# BaoFengTRRSAdapter-Example.net
KiCad netlist of a schematic drawn in EAGLE
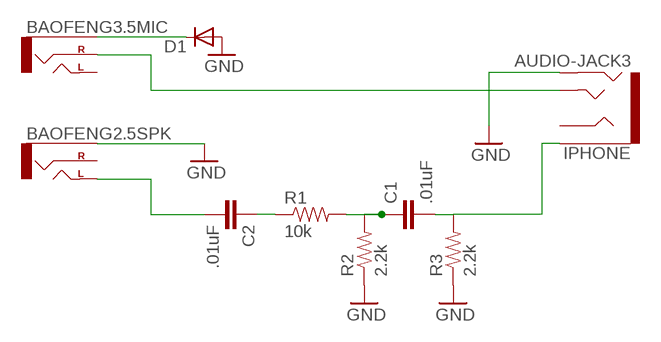
[diagram p0: schematic, sheet 1]

(export (version "E")
  (design (tool "Eeschema 10.0.6"))
  (components
    (comp (ref "BAOFENG2.5SPK")
      (value "AUDIO-JACK2.5MM")
      (footprint "eagle-import:STEREOJACK2.5MM_STEREOJACK2.5MM")
      (libsource (lib "eagle-import") (part "AUDIO-JACK2.5MM"))
    )
    (comp (ref "BAOFENG3.5MIC")
      (value "AUDIO-JACKHOLESONLY")
      (footprint "eagle-import:STEREOJACK2.5MM_SPECIAL_HOLES-ONLY")
      (libsource (lib "eagle-import") (part "AUDIO-JACKHOLESONLY"))
    )
    (comp (ref "C1")
      (value ".01uF")
      (footprint "eagle-import:0603-CAP")
      (libsource (lib "eagle-import") (part "CAP0603-CAP"))
    )
    (comp (ref "C2")
      (value ".01uF")
      (footprint "eagle-import:0603-CAP")
      (libsource (lib "eagle-import") (part "CAP0603-CAP"))
    )
    (comp (ref "D1")
      (value "DIODE1N4148")
      (footprint "eagle-import:DIODE-1N4148")
      (libsource (lib "eagle-import") (part "DIODE1N4148"))
    )
    (comp (ref "IPHONE")
      (value "AUDIO-JACK3")
      (footprint "eagle-import:AUDIO-JACK-TRRS-SMD")
      (libsource (lib "eagle-import") (part "AUDIO-JACK3"))
    )
    (comp (ref "R1")
      (value "10k")
      (footprint "eagle-import:0603-RES")
      (libsource (lib "eagle-import") (part "RESISTOR0603-RES"))
    )
    (comp (ref "R2")
      (value "2.2k")
      (footprint "eagle-import:0603-RES")
      (libsource (lib "eagle-import") (part "RESISTOR0603-RES"))
    )
    (comp (ref "R3")
      (value "2.2k")
      (footprint "eagle-import:0603-RES")
      (libsource (lib "eagle-import") (part "RESISTOR0603-RES"))
    )
  )
  (nets
    (net (code "1") (name "GND") (class "Default")
      (node (ref "BAOFENG2.5SPK") (pin "RING1") (pinfunction "SLEEVE_RING1") (pintype "bidirectional"))
      (node (ref "D1") (pin "A") (pinfunction "A_A") (pintype "passive"))
      (node (ref "IPHONE") (pin "RING2") (pinfunction "RING2_RING2") (pintype "bidirectional"))
      (node (ref "R2") (pin "1") (pinfunction "1_1") (pintype "passive"))
      (node (ref "R3") (pin "1") (pinfunction "1_1") (pintype "passive"))
    )
    (net (code "2") (name "Net-(BAOFENG2.5SPK-LEFT)") (class "Default")
      (node (ref "BAOFENG2.5SPK") (pin "SHIELD") (pinfunction "LEFT_SHIELD") (pintype "bidirectional"))
      (node (ref "C2") (pin "2") (pinfunction "2_2") (pintype "passive"))
    )
    (net (code "3") (name "Net-(BAOFENG3.5MIC-RIGHT)") (class "Default")
      (node (ref "BAOFENG3.5MIC") (pin "TIP") (pinfunction "RIGHT_TIP") (pintype "bidirectional"))
      (node (ref "IPHONE") (pin "TIP") (pinfunction "TIP_TIP") (pintype "bidirectional"))
    )
    (net (code "4") (name "Net-(BAOFENG3.5MIC-SLEEVE)") (class "Default")
      (node (ref "BAOFENG3.5MIC") (pin "RING1") (pinfunction "SLEEVE_RING1") (pintype "bidirectional"))
      (node (ref "D1") (pin "C") (pinfunction "C_C") (pintype "passive"))
    )
    (net (code "5") (name "Net-(C1-Pad1)") (class "Default")
      (node (ref "C1") (pin "1") (pinfunction "1_1") (pintype "passive"))
      (node (ref "R1") (pin "2") (pinfunction "2_2") (pintype "passive"))
      (node (ref "R2") (pin "2") (pinfunction "2_2") (pintype "passive"))
    )
    (net (code "6") (name "Net-(C1-Pad2)") (class "Default")
      (node (ref "C1") (pin "2") (pinfunction "2_2") (pintype "passive"))
      (node (ref "IPHONE") (pin "EARTH") (pinfunction "EARTH_EARTH") (pintype "bidirectional"))
      (node (ref "R3") (pin "2") (pinfunction "2_2") (pintype "passive"))
    )
    (net (code "7") (name "Net-(C2-Pad1)") (class "Default")
      (node (ref "C2") (pin "1") (pinfunction "1_1") (pintype "passive"))
      (node (ref "R1") (pin "1") (pinfunction "1_1") (pintype "passive"))
    )
    (net (code "8") (name "unconnected-(BAOFENG2.5SPK-RIGHT-PadTIP)") (class "Default")
      (node (ref "BAOFENG2.5SPK") (pin "TIP") (pinfunction "RIGHT_TIP") (pintype "bidirectional"))
    )
    (net (code "9") (name "unconnected-(BAOFENG3.5MIC-LEFT-PadSHIELD)") (class "Default")
      (node (ref "BAOFENG3.5MIC") (pin "SHIELD") (pinfunction "LEFT_SHIELD") (pintype "bidirectional"))
    )
    (net (code "10") (name "unconnected-(IPHONE-PadRING1)") (class "Default")
      (node (ref "IPHONE") (pin "RING1") (pinfunction "RING1_RING1") (pintype "bidirectional"))
    )
  )
)
